# Rotary_Encoder_Board.net
KiCad netlist of a schematic drawn in EasyEDA
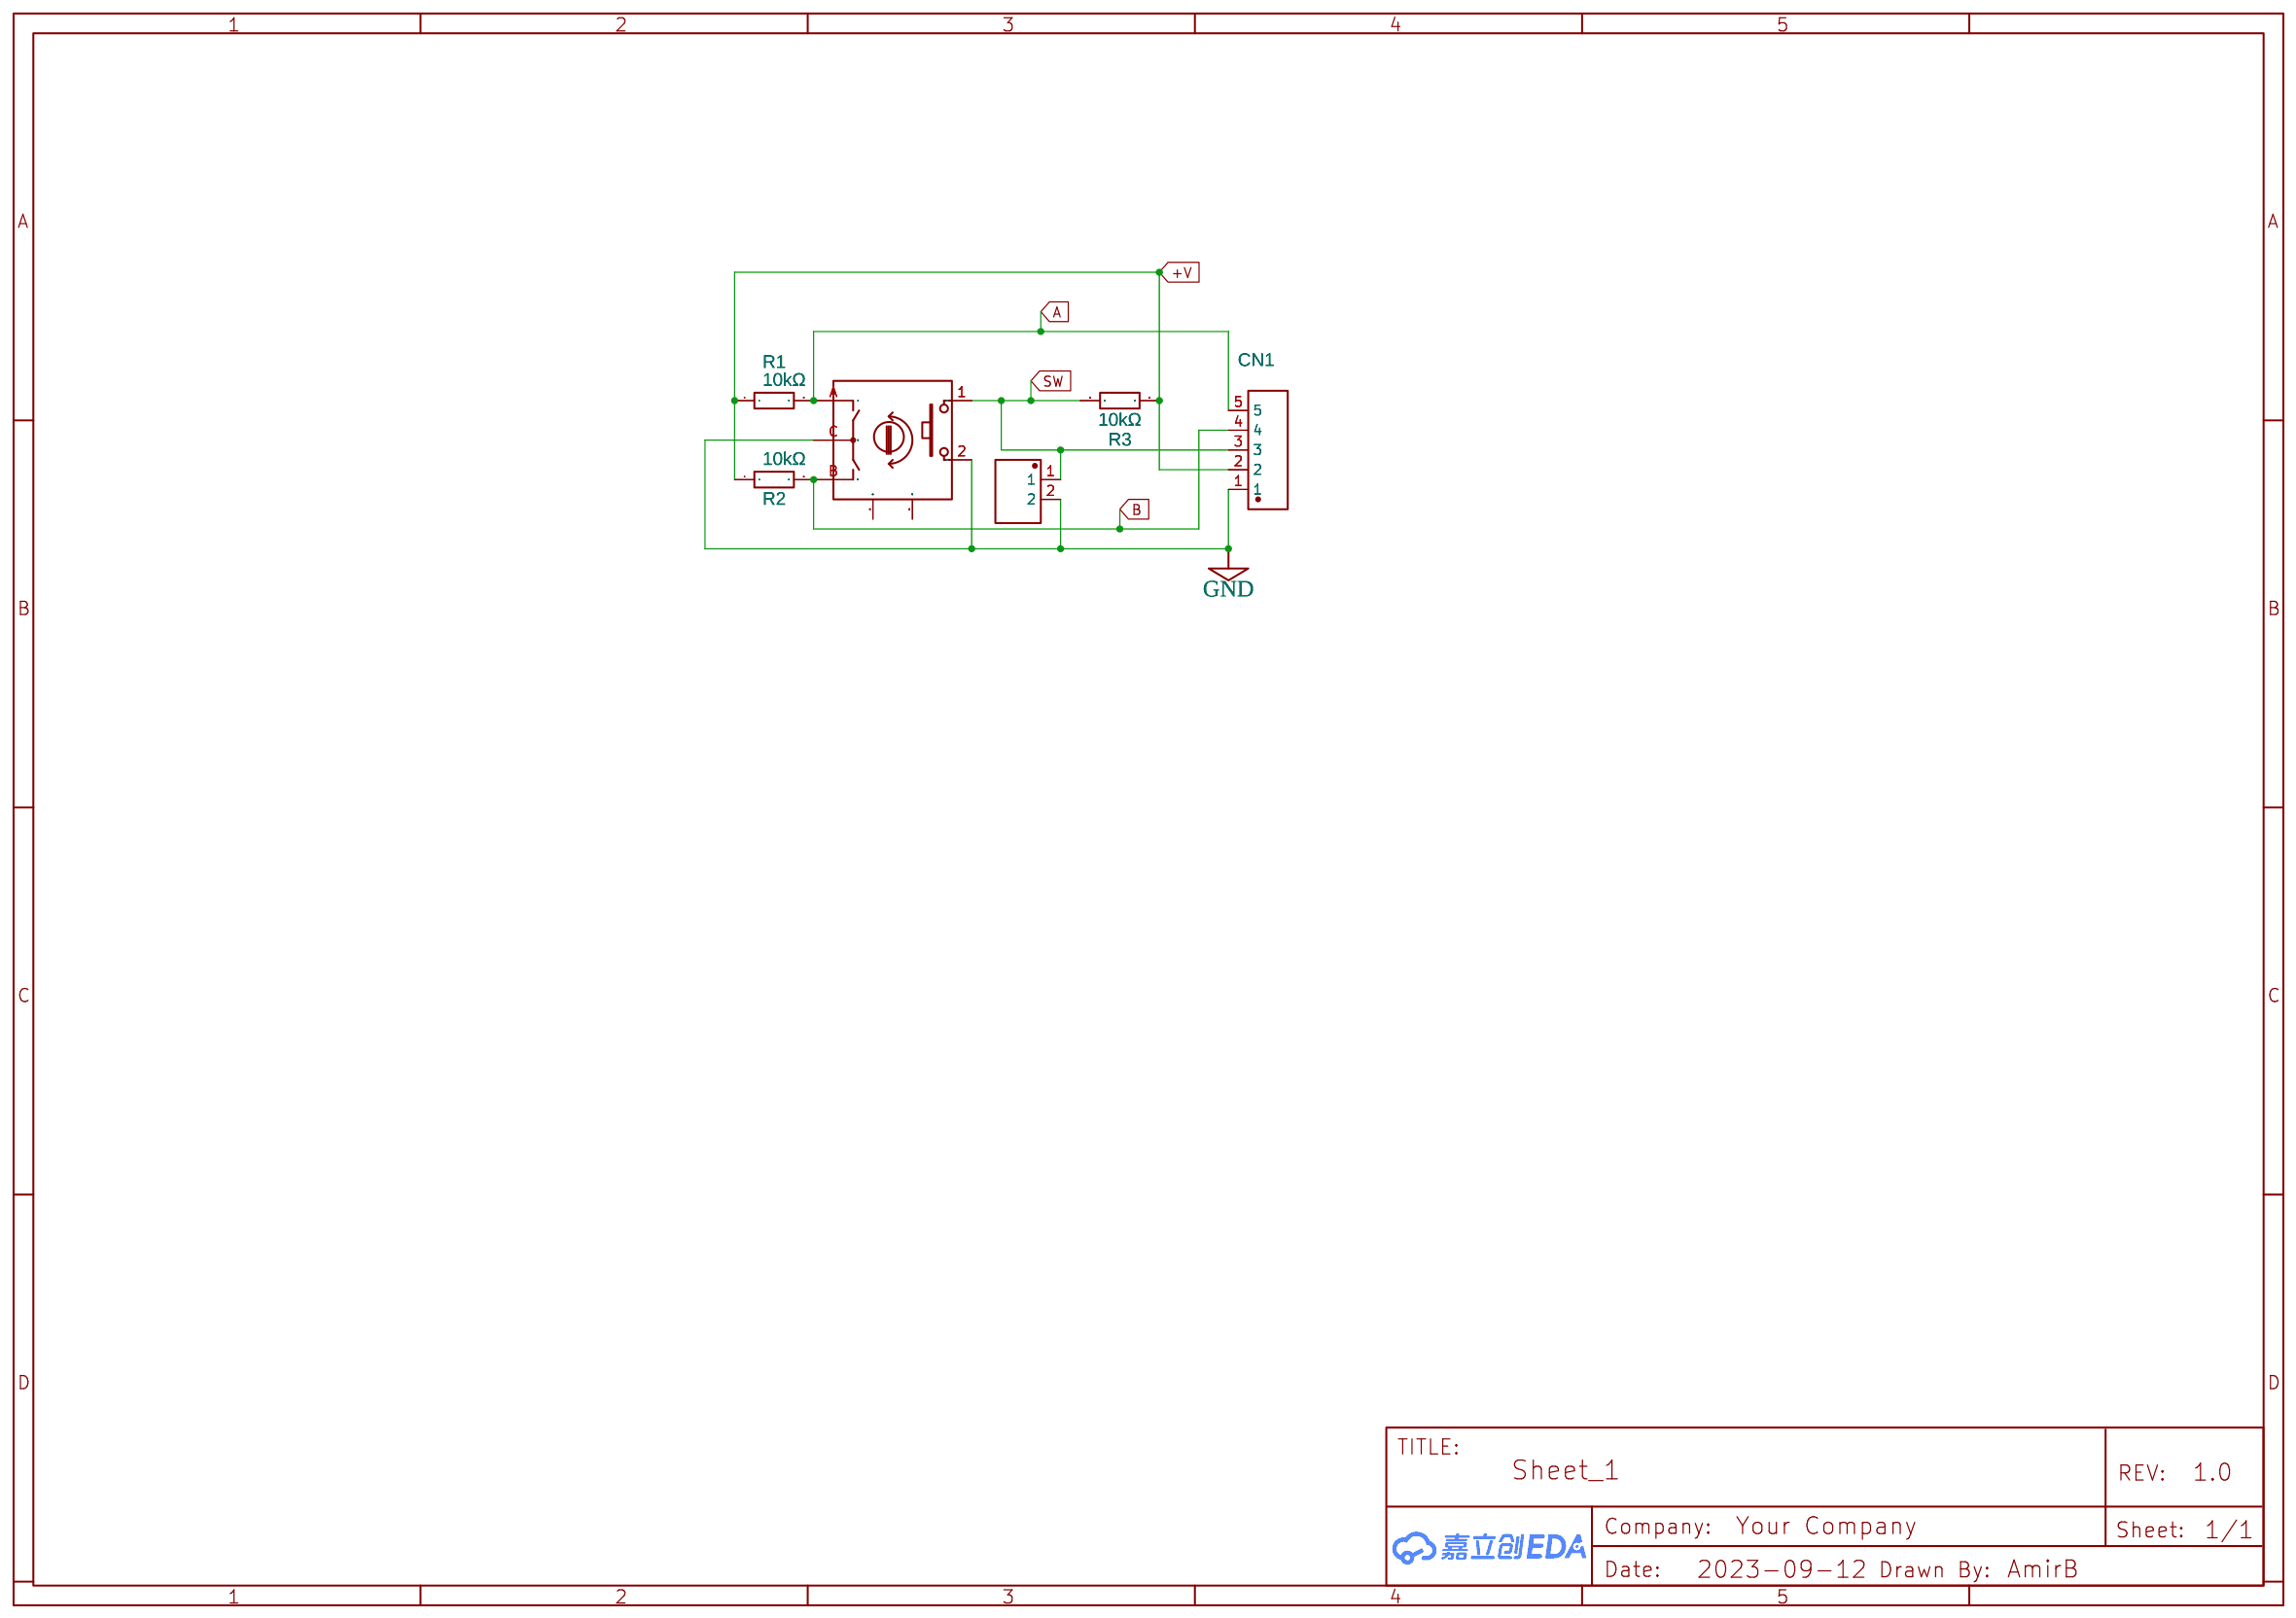
[diagram p0: schematic sheet]

(export (version "E")
  (design (tool "Eeschema 10.0.6"))
  (components
    (comp (ref "CN1")
      (value "XH-5AW_C722878")
      (fields (field (name "Manufacturer Part") "XH-5AW") (field (name "Manufacturer") "CAX"))
      (libsource (lib "") (part "XH-5AW_C722878"))
    )
    (comp (ref "R1")
      (value "10kΩ")
      (fields
        (field (name "Manufacturer Part") "0603WAF1002T5E")
        (field (name "Manufacturer") "UNI-ROYAL(厚声)")
      )
      (libsource (lib "") (part "0603WAF1002T5E_1"))
    )
    (comp (ref "R2")
      (value "10kΩ")
      (fields
        (field (name "Manufacturer Part") "0603WAF1002T5E")
        (field (name "Manufacturer") "UNI-ROYAL(厚声)")
      )
      (libsource (lib "") (part "0603WAF1002T5E_1"))
    )
    (comp (ref "R3")
      (value "10kΩ")
      (fields
        (field (name "Manufacturer Part") "0603WAF1002T5E")
        (field (name "Manufacturer") "UNI-ROYAL(厚声)")
      )
      (libsource (lib "") (part "0603WAF1002T5E"))
    )
    (comp (ref "SW1")
      (value "PEC11R-4015F-S0024")
      (fields (field (name "Manufacturer") "BOURNS"))
      (libsource (lib "") (part "PEC11R-4015F-S0024"))
    )
    (comp (ref "VIN1")
      (value "640456-2")
      (fields (field (name "BOM_Supplier Part") "C86502"))
      (libsource (lib "") (part "640456-2"))
    )
  )
  (nets
    (net (code "1") (name "+V") (class "Default")
      (node (ref "CN1") (pin "2") (pinfunction "2_2") (pintype "unspecified"))
      (node (ref "R1") (pin "1") (pinfunction "1_1") (pintype "input"))
      (node (ref "R2") (pin "1") (pinfunction "1_1") (pintype "input"))
      (node (ref "R3") (pin "1") (pinfunction "1_1") (pintype "input"))
    )
    (net (code "2") (name "A") (class "Default")
      (node (ref "CN1") (pin "5") (pinfunction "5_5") (pintype "unspecified"))
      (node (ref "R1") (pin "2") (pinfunction "2_2") (pintype "input"))
      (node (ref "SW1") (pin "A") (pinfunction "A_A") (pintype "unspecified"))
    )
    (net (code "3") (name "B") (class "Default")
      (node (ref "CN1") (pin "4") (pinfunction "4_4") (pintype "unspecified"))
      (node (ref "R2") (pin "2") (pinfunction "2_2") (pintype "input"))
      (node (ref "SW1") (pin "B") (pinfunction "B_B") (pintype "unspecified"))
    )
    (net (code "4") (name "GND") (class "Default")
      (node (ref "CN1") (pin "1") (pinfunction "1_1") (pintype "unspecified"))
      (node (ref "SW1") (pin "2") (pinfunction "2_2") (pintype "unspecified"))
      (node (ref "SW1") (pin "C") (pinfunction "C_C") (pintype "unspecified"))
      (node (ref "VIN1") (pin "2") (pinfunction "2_2") (pintype "unspecified"))
    )
    (net (code "5") (name "SW") (class "Default")
      (node (ref "CN1") (pin "3") (pinfunction "3_3") (pintype "unspecified"))
      (node (ref "R3") (pin "2") (pinfunction "2_2") (pintype "input"))
      (node (ref "SW1") (pin "1") (pinfunction "1_1") (pintype "unspecified"))
      (node (ref "VIN1") (pin "1") (pinfunction "1_1") (pintype "unspecified"))
    )
    (net (code "6") (name "unconnected-(SW1-PadMT1)") (class "Default")
      (node (ref "SW1") (pin "MT1") (pinfunction "MT1_MT1") (pintype "unspecified"))
    )
    (net (code "7") (name "unconnected-(SW1-PadMT2)") (class "Default")
      (node (ref "SW1") (pin "MT2") (pinfunction "MT2_MT2") (pintype "unspecified"))
    )
  )
)
